# Dimmer.net
KiCad netlist of a schematic drawn in EAGLE
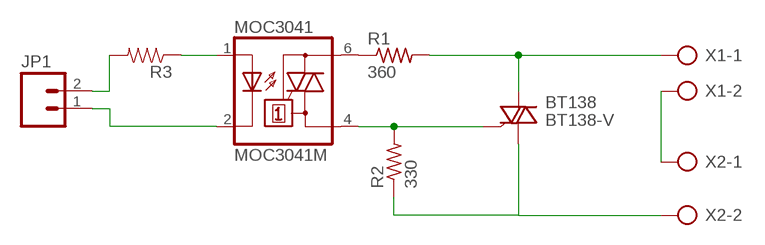
[diagram p0: schematic, sheet 1]

(export (version "E")
  (design (tool "Eeschema 10.0.6"))
  (components
    (comp (ref "BT138")
      (value "BT138-V")
      (footprint "eagle-import:TO220BV")
      (libsource (lib "eagle-import") (part "BT138-V"))
    )
    (comp (ref "JP1")
      (value "M02PTH")
      (footprint "eagle-import:1X02")
      (libsource (lib "eagle-import") (part "M02PTH"))
    )
    (comp (ref "MOC3041")
      (value "MOC3041M")
      (footprint "eagle-import:DIL06")
      (fields (field (name "MF") "FAIRCHILD SEMICONDUCTOR"))
      (libsource (lib "eagle-import") (part "MOC3041M"))
    )
    (comp (ref "R1")
      (value "360")
      (footprint "eagle-import:0309V")
      (libsource (lib "eagle-import") (part "R-US_0309/V"))
    )
    (comp (ref "R2")
      (value "330")
      (footprint "eagle-import:0309V")
      (libsource (lib "eagle-import") (part "R-US_0309/V"))
    )
    (comp (ref "R3")
      (value "RESISTOR0603-RES")
      (footprint "eagle-import:0603-RES")
      (libsource (lib "eagle-import") (part "RESISTOR0603-RES"))
    )
    (comp (ref "X1")
      (value "AK500/2")
      (footprint "eagle-import:AK500_2")
      (libsource (lib "eagle-import") (part "AK500/2"))
    )
    (comp (ref "X2")
      (value "AK500/2")
      (footprint "eagle-import:AK500_2")
      (libsource (lib "eagle-import") (part "AK500/2"))
    )
  )
  (nets
    (net (code "1") (name "Net-(BT138-A1)") (class "Default")
      (node (ref "BT138") (pin "T1") (pinfunction "A1_T1") (pintype "passive"))
      (node (ref "R2") (pin "1") (pinfunction "1_1") (pintype "passive"))
      (node (ref "X2") (pin "2") (pinfunction "KL_2") (pintype "passive"))
    )
    (net (code "2") (name "Net-(BT138-A2)") (class "Default")
      (node (ref "BT138") (pin "T2") (pinfunction "A2_T2") (pintype "passive"))
      (node (ref "R1") (pin "2") (pinfunction "2_2") (pintype "passive"))
      (node (ref "X1") (pin "1") (pinfunction "KL_1") (pintype "passive"))
    )
    (net (code "3") (name "Net-(JP1-Pad2)") (class "Default")
      (node (ref "JP1") (pin "2") (pinfunction "2_2") (pintype "passive"))
      (node (ref "R3") (pin "2") (pinfunction "2_2") (pintype "passive"))
    )
    (net (code "4") (name "Net-(MOC3041-A)") (class "Default")
      (node (ref "MOC3041") (pin "1") (pinfunction "A_1") (pintype "passive"))
      (node (ref "R3") (pin "1") (pinfunction "1_1") (pintype "passive"))
    )
    (net (code "5") (name "Net-(MOC3041-A1)") (class "Default")
      (node (ref "BT138") (pin "G") (pinfunction "G_G") (pintype "passive"))
      (node (ref "MOC3041") (pin "4") (pinfunction "A1_4") (pintype "passive"))
      (node (ref "R2") (pin "2") (pinfunction "2_2") (pintype "passive"))
    )
    (net (code "6") (name "Net-(MOC3041-A2)") (class "Default")
      (node (ref "MOC3041") (pin "6") (pinfunction "A2_6") (pintype "passive"))
      (node (ref "R1") (pin "1") (pinfunction "1_1") (pintype "passive"))
    )
    (net (code "7") (name "Net-(MOC3041-C)") (class "Default")
      (node (ref "JP1") (pin "1") (pinfunction "1_1") (pintype "passive"))
      (node (ref "MOC3041") (pin "2") (pinfunction "C_2") (pintype "passive"))
    )
    (net (code "8") (name "Net-(X1B-KL)") (class "Default")
      (node (ref "X1") (pin "2") (pinfunction "KL_2") (pintype "passive"))
      (node (ref "X2") (pin "1") (pinfunction "KL_1") (pintype "passive"))
    )
  )
)
